# Connectors.net
KiCad netlist of a schematic drawn in Altium Designer
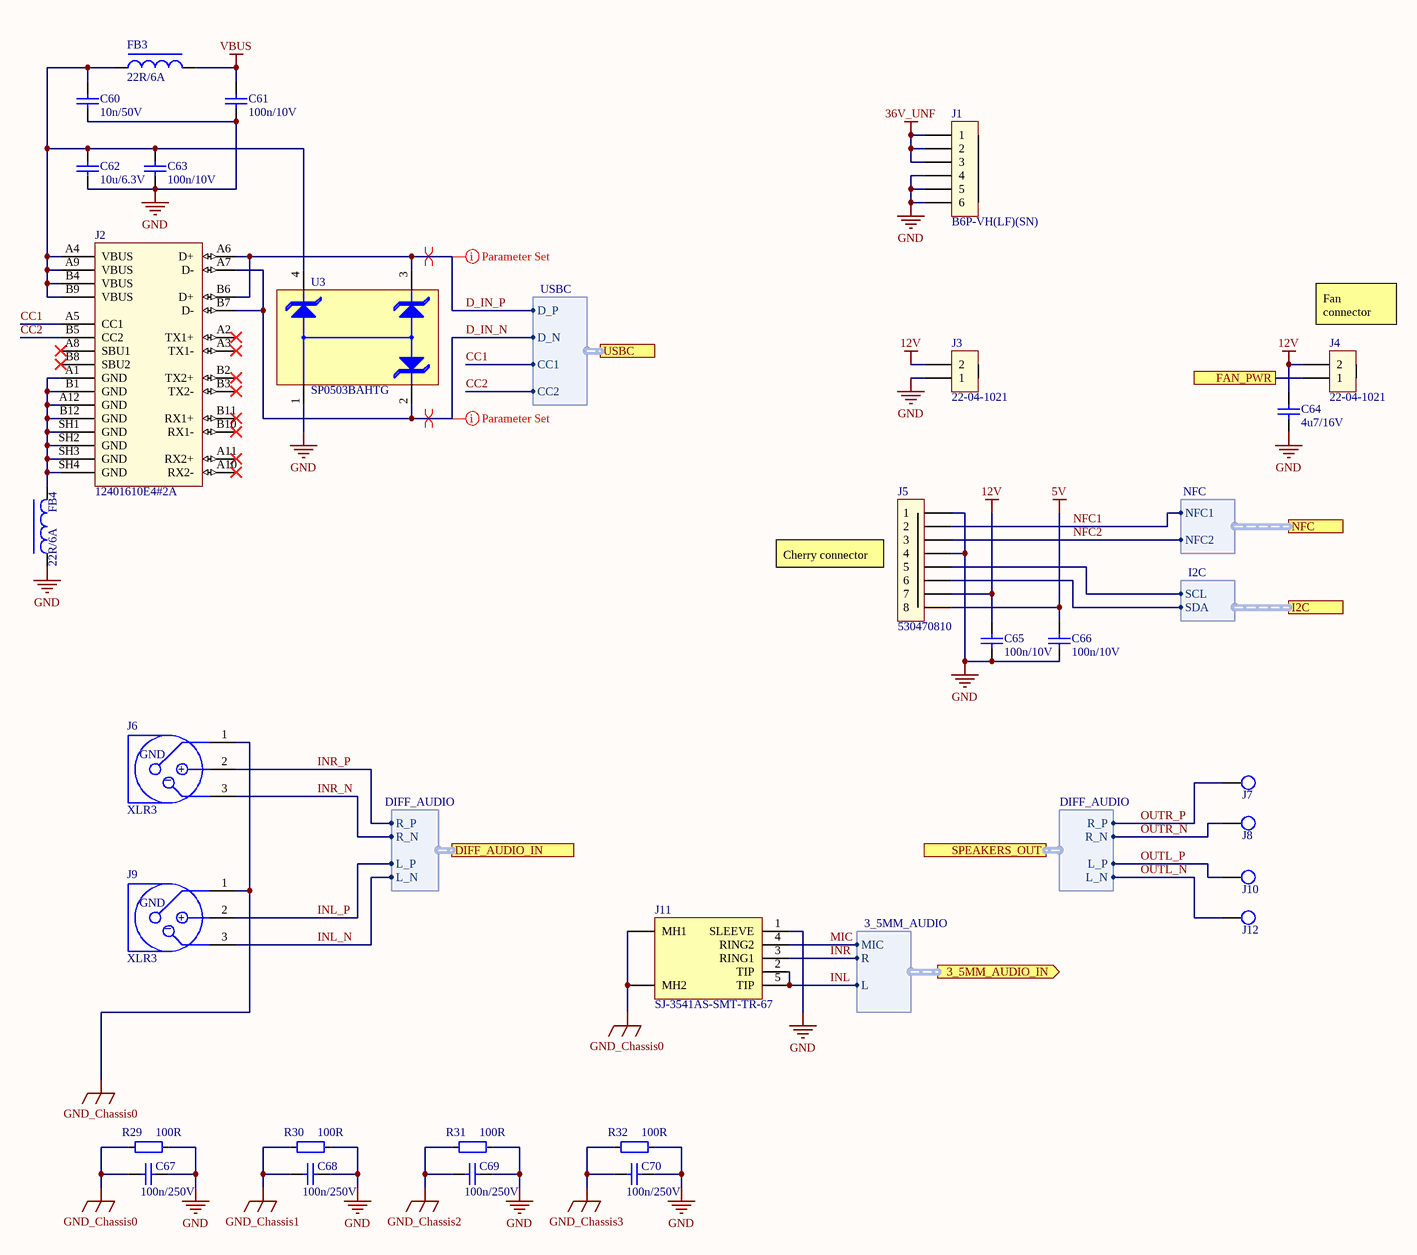
[diagram p0: Connectors.SchDoc]

(export (version "E")
  (design (tool "Eeschema 10.0.6"))
  (components
    (comp (ref "C60")
      (value "10n/50V")
      (footprint "C0402")
      (fields (field (name "VOLTAGE") "50V") (field (name "TOLERANCE") "10%"))
      (libsource (lib "dk_capacitors") (part "10n 50V X7R 0402"))
    )
    (comp (ref "C61")
      (value "100n/10V")
      (footprint "C0402")
      (fields (field (name "VOLTAGE") "10V") (field (name "TOLERANCE") "20%"))
      (libsource (lib "dk_capacitors") (part "100n 10V X5R 0402"))
    )
    (comp (ref "C62")
      (value "10u/6.3V")
      (footprint "C0805")
      (fields (field (name "VOLTAGE") "6.3V") (field (name "TOLERANCE") "10%"))
      (libsource (lib "dk_capacitors") (part "10u 6V3 X7R 0805"))
    )
    (comp (ref "C63")
      (value "100n/10V")
      (footprint "C0402")
      (fields (field (name "VOLTAGE") "10V") (field (name "TOLERANCE") "20%"))
      (libsource (lib "dk_capacitors") (part "100n 10V X5R 0402"))
    )
    (comp (ref "C64")
      (value "4u7/16V")
      (footprint "C0805")
      (fields (field (name "VOLTAGE") "16V") (field (name "TOLERANCE") "10%"))
      (libsource (lib "dk_capacitors") (part "4u7 16V X7R 0805"))
    )
    (comp (ref "C65")
      (value "100n/10V")
      (footprint "C0402")
      (fields (field (name "VOLTAGE") "10V") (field (name "TOLERANCE") "20%"))
      (libsource (lib "dk_capacitors") (part "100n 10V X5R 0402"))
    )
    (comp (ref "C66")
      (value "100n/10V")
      (footprint "C0402")
      (fields (field (name "VOLTAGE") "10V") (field (name "TOLERANCE") "20%"))
      (libsource (lib "dk_capacitors") (part "100n 10V X5R 0402"))
    )
    (comp (ref "C67")
      (value "100n/250V")
      (footprint "C1210")
      (fields (field (name "VOLTAGE") "250V") (field (name "TOLERANCE") "10%"))
      (libsource (lib "dk_capacitors") (part "100n 250V X7R 1206"))
    )
    (comp (ref "C68")
      (value "100n/250V")
      (footprint "C1210")
      (fields (field (name "VOLTAGE") "250V") (field (name "TOLERANCE") "10%"))
      (libsource (lib "dk_capacitors") (part "100n 250V X7R 1206"))
    )
    (comp (ref "C69")
      (value "100n/250V")
      (footprint "C1210")
      (fields (field (name "VOLTAGE") "250V") (field (name "TOLERANCE") "10%"))
      (libsource (lib "dk_capacitors") (part "100n 250V X7R 1206"))
    )
    (comp (ref "C70")
      (value "100n/250V")
      (footprint "C1210")
      (fields (field (name "VOLTAGE") "250V") (field (name "TOLERANCE") "10%"))
      (libsource (lib "dk_capacitors") (part "100n 250V X7R 1206"))
    )
    (comp (ref "FB3")
      (value "22R/6A")
      (footprint "FB0805")
      (description "22 Ohms @ 100MHz 1 Power Line Ferrite Bead 0805 (2012 Metric) 6A 9mOhm")
      (fields (field (name "MANUFACTURER PART NUMBER") "BLM21PG220SN1D") (field (name "TOLERANCE") "25%"))
      (libsource (lib "dk_inductors") (part "BLM21PG220SN1D"))
    )
    (comp (ref "FB4")
      (value "22R/6A")
      (footprint "FB0805")
      (description "22 Ohms @ 100MHz 1 Power Line Ferrite Bead 0805 (2012 Metric) 6A 9mOhm")
      (fields (field (name "MANUFACTURER PART NUMBER") "BLM21PG220SN1D") (field (name "TOLERANCE") "25%"))
      (libsource (lib "dk_inductors") (part "BLM21PG220SN1D"))
    )
    (comp (ref "J1")
      (value "B6P-VH(LF)(SN)")
      (footprint "B6P-VH")
      (description "Pin Header, Wire-to-Board, 3.96 mm, 1 Rows, 6 Contacts, Through Hole Straight, VH Series")
      (libsource (lib "dk_connectors") (part "B6P-VH(LF)(SN)"))
    )
    (comp (ref "J2")
      (value "12401610E4#2A")
      (footprint "12401610E4#2A")
      (description "USB Connectors USB TYPE C RCPT R/A SMT TOP MOUNT")
      (libsource (lib "dk_connectors") (part "12401610E4#2A"))
    )
    (comp (ref "J3")
      (value "22-04-1021")
      (footprint "22-04-1021")
      (description "Pin Header, Wire-to-Board, 2.5 mm, 1 Rows, 2 Contacts, Through Hole Straight, KK 5045 Series")
      (libsource (lib "dk_connectors") (part "22-04-1021"))
    )
    (comp (ref "J4")
      (value "22-04-1021")
      (footprint "22-04-1021")
      (description "Pin Header, Wire-to-Board, 2.5 mm, 1 Rows, 2 Contacts, Through Hole Straight, KK 5045 Series")
      (libsource (lib "dk_connectors") (part "22-04-1021"))
    )
    (comp (ref "J5")
      (value "530470810")
      (footprint "530470810")
      (libsource (lib "dk_connectors") (part "530470810"))
    )
    (comp (ref "J6")
      (value "XLR3")
      (footprint "NC3FAAH1")
      (description "XLR Connectors 3P FEMALE HORIZ PIN 1 & GRD TOGETHER")
      (libsource (lib "dk_connectors") (part "NC3FAAH1"))
    )
    (comp (ref "J7")
      (value "AUDIO_JACK")
      (footprint "AUDIO_JACK_RED")
      (description "Speaker Spade Terminal Binding Post Metal Banana Plug Socket Connector")
      (libsource (lib "dk_connectors") (part "AUDIO_JACK"))
    )
    (comp (ref "J8")
      (value "AUDIO_JACK")
      (footprint "AUDIO_JACK_BLACK")
      (description "Speaker Spade Terminal Binding Post Metal Banana Plug Socket Connector")
      (libsource (lib "dk_connectors") (part "AUDIO_JACK"))
    )
    (comp (ref "J9")
      (value "XLR3")
      (footprint "NC3FAAH1")
      (description "XLR Connectors 3P FEMALE HORIZ PIN 1 & GRD TOGETHER")
      (libsource (lib "dk_connectors") (part "NC3FAAH1"))
    )
    (comp (ref "J10")
      (value "AUDIO_JACK")
      (footprint "AUDIO_JACK_RED")
      (description "Speaker Spade Terminal Binding Post Metal Banana Plug Socket Connector")
      (libsource (lib "dk_connectors") (part "AUDIO_JACK"))
    )
    (comp (ref "J11")
      (value "SJ-3541AS-SMT-TR-67")
      (footprint "SJ-3541AS-SMT-TR-67")
      (description "3.50mm (0.141\", 1/8\", Mini Plug) - Headphone Phone Jack 5 Conductor (TRRRS) Connector Solder")
      (libsource (lib "dk_connectors") (part "SJ-3541AS-SMT-TR-67"))
    )
    (comp (ref "J12")
      (value "AUDIO_JACK")
      (footprint "AUDIO_JACK_BLACK")
      (description "Speaker Spade Terminal Binding Post Metal Banana Plug Socket Connector")
      (libsource (lib "dk_connectors") (part "AUDIO_JACK"))
    )
    (comp (ref "R29")
      (value "100R")
      (footprint "R1206")
      (fields (field (name "TOLERANCE") "1%") (field (name "VOLTAGE") "200V"))
      (libsource (lib "dk_resistors") (part "100R 250mW 200V 1206"))
    )
    (comp (ref "R30")
      (value "100R")
      (footprint "R1206")
      (fields (field (name "TOLERANCE") "1%") (field (name "VOLTAGE") "200V"))
      (libsource (lib "dk_resistors") (part "100R 250mW 200V 1206"))
    )
    (comp (ref "R31")
      (value "100R")
      (footprint "R1206")
      (fields (field (name "TOLERANCE") "1%") (field (name "VOLTAGE") "200V"))
      (libsource (lib "dk_resistors") (part "100R 250mW 200V 1206"))
    )
    (comp (ref "R32")
      (value "100R")
      (footprint "R1206")
      (fields (field (name "TOLERANCE") "1%") (field (name "VOLTAGE") "200V"))
      (libsource (lib "dk_resistors") (part "100R 250mW 200V 1206"))
    )
    (comp (ref "U3")
      (value "SP0503BAHTG")
      (footprint "SOT143-4")
      (description "ESD Suppressors / TVS Diodes TVS AVAL DIODE SMT")
      (libsource (lib "dk_ic_protection") (part "SP0503BAHTG"))
    )
  )
  (nets
    (net (code "6") (name "/CC1") (class "Default")
      (node (ref "J2") (pin "A5") (pinfunction "CC1_A5") (pintype "passive"))
    )
    (net (code "7") (name "/CC2") (class "Default")
      (node (ref "J2") (pin "B5") (pinfunction "CC2_B5") (pintype "passive"))
    )
    (net (code "8") (name "/D_IN_N") (class "Default")
      (node (ref "J2") (pin "A7") (pinfunction "D-_A7") (pintype "bidirectional"))
      (node (ref "J2") (pin "B7") (pinfunction "D-_B7") (pintype "bidirectional"))
      (node (ref "U3") (pin "2") (pintype "passive"))
    )
    (net (code "9") (name "/D_IN_P") (class "Default")
      (node (ref "J2") (pin "A6") (pinfunction "D+_A6") (pintype "bidirectional"))
      (node (ref "J2") (pin "B6") (pinfunction "D+_B6") (pintype "bidirectional"))
      (node (ref "U3") (pin "3") (pintype "passive"))
    )
    (net (code "10") (name "/FAN_PWR") (class "Default")
      (node (ref "J4") (pin "1") (pinfunction "1_1") (pintype "passive"))
    )
    (net (code "11") (name "/INL") (class "Default")
      (node (ref "J11") (pin "2") (pinfunction "TIP_2") (pintype "passive"))
      (node (ref "J11") (pin "5") (pinfunction "TIP_5") (pintype "passive"))
    )
    (net (code "12") (name "/INL_N") (class "Default")
      (node (ref "J9") (pin "3") (pinfunction "-_3") (pintype "passive"))
    )
    (net (code "13") (name "/INL_P") (class "Default")
      (node (ref "J9") (pin "2") (pinfunction "+_2") (pintype "passive"))
    )
    (net (code "14") (name "/INR") (class "Default")
      (node (ref "J11") (pin "3") (pinfunction "RING1_3") (pintype "passive"))
    )
    (net (code "15") (name "/INR_N") (class "Default")
      (node (ref "J6") (pin "3") (pinfunction "-_3") (pintype "passive"))
    )
    (net (code "16") (name "/INR_P") (class "Default")
      (node (ref "J6") (pin "2") (pinfunction "+_2") (pintype "passive"))
    )
    (net (code "17") (name "/MIC") (class "Default")
      (node (ref "J11") (pin "4") (pinfunction "RING2_4") (pintype "passive"))
    )
    (net (code "18") (name "/NFC1") (class "Default")
      (node (ref "J5") (pin "2") (pinfunction "2_2") (pintype "passive"))
    )
    (net (code "19") (name "/NFC2") (class "Default")
      (node (ref "J5") (pin "3") (pinfunction "3_3") (pintype "passive"))
    )
    (net (code "20") (name "/OUTL_N") (class "Default") (node (ref "J12") (pin "1") (pintype "passive")))
    (net (code "21") (name "/OUTL_P") (class "Default") (node (ref "J10") (pin "1") (pintype "passive")))
    (net (code "22") (name "/OUTR_N") (class "Default") (node (ref "J8") (pin "1") (pintype "passive")))
    (net (code "23") (name "/OUTR_P") (class "Default") (node (ref "J7") (pin "1") (pintype "passive")))
    (net (code "24") (name "/SCL") (class "Default")
      (node (ref "J5") (pin "5") (pinfunction "5_5") (pintype "passive"))
    )
    (net (code "25") (name "/SDA") (class "Default")
      (node (ref "J5") (pin "6") (pinfunction "6_6") (pintype "passive"))
    )
    (net (code "31") (name "5V") (class "Default")
      (node (ref "C66") (pin "2") (pinfunction "2_2") (pintype "passive"))
      (node (ref "J5") (pin "8") (pinfunction "8_8") (pintype "passive"))
    )
    (net (code "32") (name "12V") (class "Default")
      (node (ref "C64") (pin "2") (pinfunction "2_2") (pintype "passive"))
      (node (ref "C65") (pin "2") (pinfunction "2_2") (pintype "passive"))
      (node (ref "J3") (pin "2") (pinfunction "2_2") (pintype "passive"))
      (node (ref "J4") (pin "2") (pinfunction "2_2") (pintype "passive"))
      (node (ref "J5") (pin "7") (pinfunction "7_7") (pintype "passive"))
    )
    (net (code "33") (name "36V_UNF") (class "Default")
      (node (ref "J1") (pin "1") (pinfunction "1_1") (pintype "passive"))
      (node (ref "J1") (pin "2") (pinfunction "2_2") (pintype "passive"))
      (node (ref "J1") (pin "3") (pinfunction "3_3") (pintype "passive"))
    )
    (net (code "34") (name "GND") (class "Default")
      (node (ref "C60") (pin "1") (pinfunction "1_1") (pintype "passive"))
      (node (ref "C61") (pin "1") (pinfunction "1_1") (pintype "passive"))
      (node (ref "C62") (pin "1") (pinfunction "1_1") (pintype "passive"))
      (node (ref "C63") (pin "1") (pinfunction "1_1") (pintype "passive"))
      (node (ref "C64") (pin "1") (pinfunction "1_1") (pintype "passive"))
      (node (ref "C65") (pin "1") (pinfunction "1_1") (pintype "passive"))
      (node (ref "C66") (pin "1") (pinfunction "1_1") (pintype "passive"))
      (node (ref "C67") (pin "2") (pinfunction "2_2") (pintype "passive"))
      (node (ref "C68") (pin "2") (pinfunction "2_2") (pintype "passive"))
      (node (ref "C69") (pin "2") (pinfunction "2_2") (pintype "passive"))
      (node (ref "C70") (pin "2") (pinfunction "2_2") (pintype "passive"))
      (node (ref "FB4") (pin "1") (pinfunction "1_1") (pintype "passive"))
      (node (ref "J1") (pin "4") (pinfunction "4_4") (pintype "passive"))
      (node (ref "J1") (pin "5") (pinfunction "5_5") (pintype "passive"))
      (node (ref "J1") (pin "6") (pinfunction "6_6") (pintype "passive"))
      (node (ref "J11") (pin "1") (pinfunction "SLEEVE_1") (pintype "passive"))
      (node (ref "J3") (pin "1") (pinfunction "1_1") (pintype "passive"))
      (node (ref "J5") (pin "1") (pinfunction "1_1") (pintype "passive"))
      (node (ref "J5") (pin "4") (pinfunction "4_4") (pintype "passive"))
      (node (ref "R29") (pin "2") (pinfunction "2_2") (pintype "passive"))
      (node (ref "R30") (pin "2") (pinfunction "2_2") (pintype "passive"))
      (node (ref "R31") (pin "2") (pinfunction "2_2") (pintype "passive"))
      (node (ref "R32") (pin "2") (pinfunction "2_2") (pintype "passive"))
      (node (ref "U3") (pin "1") (pintype "passive"))
    )
    (net (code "35") (name "GND_Chassis0") (class "Default")
      (node (ref "C67") (pin "1") (pinfunction "1_1") (pintype "passive"))
      (node (ref "J11") (pin "MH1") (pinfunction "MH1_MH1") (pintype "passive"))
      (node (ref "J11") (pin "MH2") (pinfunction "MH2_MH2") (pintype "passive"))
      (node (ref "J6") (pin "1") (pinfunction "GND_1") (pintype "passive"))
      (node (ref "J9") (pin "1") (pinfunction "GND_1") (pintype "passive"))
      (node (ref "R29") (pin "1") (pinfunction "1_1") (pintype "passive"))
    )
    (net (code "36") (name "GND_Chassis1") (class "Default")
      (node (ref "C68") (pin "1") (pinfunction "1_1") (pintype "passive"))
      (node (ref "R30") (pin "1") (pinfunction "1_1") (pintype "passive"))
    )
    (net (code "37") (name "GND_Chassis2") (class "Default")
      (node (ref "C69") (pin "1") (pinfunction "1_1") (pintype "passive"))
      (node (ref "R31") (pin "1") (pinfunction "1_1") (pintype "passive"))
    )
    (net (code "38") (name "GND_Chassis3") (class "Default")
      (node (ref "C70") (pin "1") (pinfunction "1_1") (pintype "passive"))
      (node (ref "R32") (pin "1") (pinfunction "1_1") (pintype "passive"))
    )
    (net (code "39") (name "Net-(C60-Pad2)") (class "Default")
      (node (ref "C60") (pin "2") (pinfunction "2_2") (pintype "passive"))
      (node (ref "C62") (pin "2") (pinfunction "2_2") (pintype "passive"))
      (node (ref "C63") (pin "2") (pinfunction "2_2") (pintype "passive"))
      (node (ref "FB3") (pin "1") (pinfunction "1_1") (pintype "passive"))
      (node (ref "J2") (pin "A4") (pinfunction "VBUS_A4") (pintype "power_in"))
      (node (ref "J2") (pin "A9") (pinfunction "VBUS_A9") (pintype "power_in"))
      (node (ref "J2") (pin "B4") (pinfunction "VBUS_B4") (pintype "power_in"))
      (node (ref "J2") (pin "B9") (pinfunction "VBUS_B9") (pintype "power_in"))
      (node (ref "U3") (pin "4") (pintype "passive"))
    )
    (net (code "40") (name "Net-(FB4-Pad2)") (class "Default")
      (node (ref "FB4") (pin "2") (pinfunction "2_2") (pintype "passive"))
      (node (ref "J2") (pin "A1") (pinfunction "GND_A1") (pintype "power_in"))
      (node (ref "J2") (pin "A12") (pinfunction "GND_A12") (pintype "power_in"))
      (node (ref "J2") (pin "B1") (pinfunction "GND_B1") (pintype "power_in"))
      (node (ref "J2") (pin "B12") (pinfunction "GND_B12") (pintype "power_in"))
      (node (ref "J2") (pin "SH1") (pinfunction "GND_SH1") (pintype "power_in"))
      (node (ref "J2") (pin "SH2") (pinfunction "GND_SH2") (pintype "power_in"))
      (node (ref "J2") (pin "SH3") (pinfunction "GND_SH3") (pintype "power_in"))
      (node (ref "J2") (pin "SH4") (pinfunction "GND_SH4") (pintype "power_in"))
    )
    (net (code "41") (name "VBUS") (class "Default")
      (node (ref "C61") (pin "2") (pinfunction "2_2") (pintype "passive"))
      (node (ref "FB3") (pin "2") (pinfunction "2_2") (pintype "passive"))
    )
    (net (code "42") (name "unconnected-(J2-RX1+-PadB11)") (class "Default")
      (node (ref "J2") (pin "B11") (pinfunction "RX1+_B11") (pintype "bidirectional+no_connect"))
    )
    (net (code "43") (name "unconnected-(J2-RX1--PadB10)") (class "Default")
      (node (ref "J2") (pin "B10") (pinfunction "RX1-_B10") (pintype "bidirectional+no_connect"))
    )
    (net (code "44") (name "unconnected-(J2-RX2+-PadA11)") (class "Default")
      (node (ref "J2") (pin "A11") (pinfunction "RX2+_A11") (pintype "bidirectional+no_connect"))
    )
    (net (code "45") (name "unconnected-(J2-RX2--PadA10)") (class "Default")
      (node (ref "J2") (pin "A10") (pinfunction "RX2-_A10") (pintype "bidirectional+no_connect"))
    )
    (net (code "46") (name "unconnected-(J2-SBU1-PadA8)") (class "Default")
      (node (ref "J2") (pin "A8") (pinfunction "SBU1_A8") (pintype "passive+no_connect"))
    )
    (net (code "47") (name "unconnected-(J2-SBU2-PadB8)") (class "Default")
      (node (ref "J2") (pin "B8") (pinfunction "SBU2_B8") (pintype "passive+no_connect"))
    )
    (net (code "48") (name "unconnected-(J2-TX1+-PadA2)") (class "Default")
      (node (ref "J2") (pin "A2") (pinfunction "TX1+_A2") (pintype "bidirectional+no_connect"))
    )
    (net (code "49") (name "unconnected-(J2-TX1--PadA3)") (class "Default")
      (node (ref "J2") (pin "A3") (pinfunction "TX1-_A3") (pintype "bidirectional+no_connect"))
    )
    (net (code "50") (name "unconnected-(J2-TX2+-PadB2)") (class "Default")
      (node (ref "J2") (pin "B2") (pinfunction "TX2+_B2") (pintype "bidirectional+no_connect"))
    )
    (net (code "51") (name "unconnected-(J2-TX2--PadB3)") (class "Default")
      (node (ref "J2") (pin "B3") (pinfunction "TX2-_B3") (pintype "bidirectional+no_connect"))
    )
  )
)
